# clapclap2313.net
KiCad netlist of a schematic drawn in EAGLE
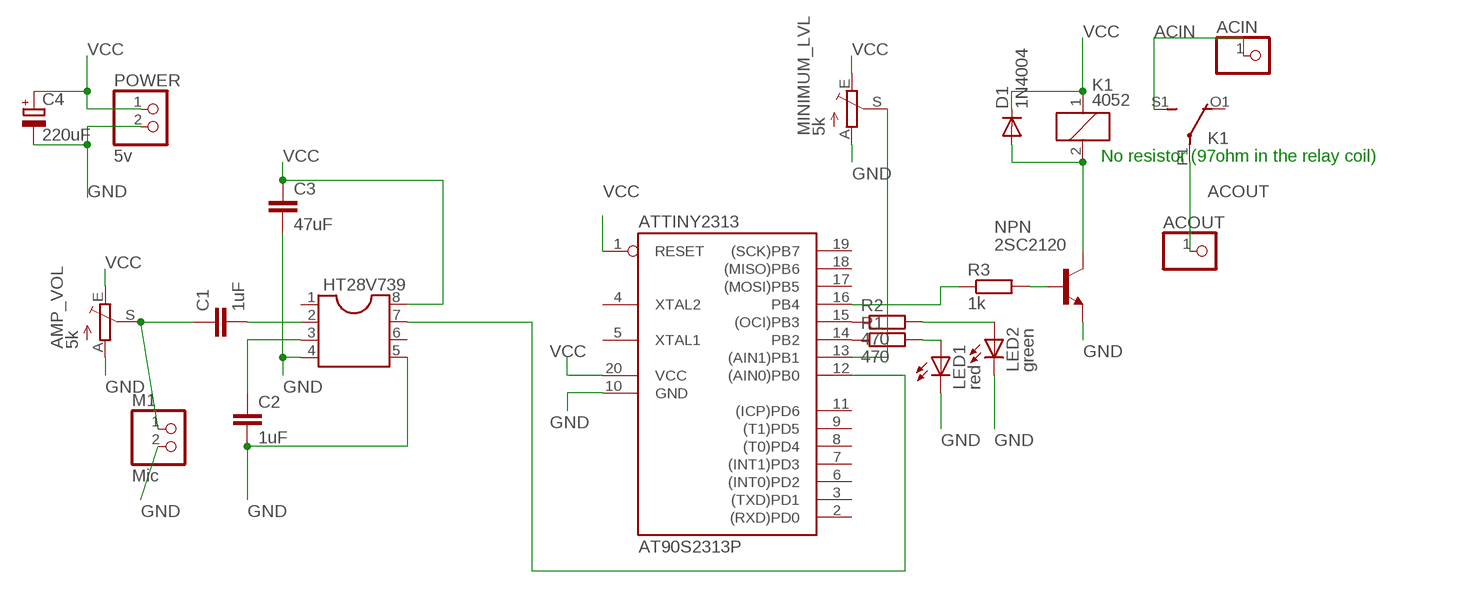
[diagram p0: schematic, sheet 1]

(export (version "E")
  (design (tool "Eeschema 10.0.6"))
  (components
    (comp (ref "ACIN")
      (value "PINHD-1X1")
      (footprint "eagle-import:1X01")
      (libsource (lib "eagle-import") (part "PINHD-1X1"))
    )
    (comp (ref "ACOUT")
      (value "PINHD-1X1")
      (footprint "eagle-import:1X01")
      (libsource (lib "eagle-import") (part "PINHD-1X1"))
    )
    (comp (ref "AMP_VOL")
      (value "5k")
      (footprint "eagle-import:CT6")
      (libsource (lib "eagle-import") (part "TRIM_EU-CT6"))
    )
    (comp (ref "ATTINY2313")
      (value "AT90S2313P")
      (footprint "eagle-import:DIL20")
      (libsource (lib "eagle-import") (part "AT90S2313P"))
    )
    (comp (ref "C1")
      (value "1uF")
      (footprint "eagle-import:C050-024X044")
      (libsource (lib "eagle-import") (part "C-EU050-024X044"))
    )
    (comp (ref "C2")
      (value "1uF")
      (footprint "eagle-import:C050-024X044")
      (libsource (lib "eagle-import") (part "C-EU050-024X044"))
    )
    (comp (ref "C3")
      (value "47uF")
      (footprint "eagle-import:C050-024X044")
      (libsource (lib "eagle-import") (part "C-EU050-024X044"))
    )
    (comp (ref "C4")
      (value "220uF")
      (footprint "eagle-import:E2,5-6E")
      (libsource (lib "eagle-import") (part "CPOL-EUE2,5-6E"))
    )
    (comp (ref "D1")
      (value "1N4004")
      (footprint "eagle-import:DO41-10")
      (libsource (lib "eagle-import") (part "1N4004"))
    )
    (comp (ref "HT28V739")
      (value "DIL8S")
      (footprint "eagle-import:SOCKET-08")
      (libsource (lib "eagle-import") (part "DIL8S"))
    )
    (comp (ref "K1")
      (value "4052")
      (footprint "eagle-import:F4052")
      (libsource (lib "eagle-import") (part "4052"))
    )
    (comp (ref "LED1")
      (value "red")
      (footprint "eagle-import:LED3MM")
      (libsource (lib "eagle-import") (part "LED3MM"))
    )
    (comp (ref "LED2")
      (value "green")
      (footprint "eagle-import:LED3MM")
      (libsource (lib "eagle-import") (part "LED3MM"))
    )
    (comp (ref "M1")
      (value "Mic")
      (footprint "eagle-import:1X02")
      (libsource (lib "eagle-import") (part "PINHD-1X2"))
    )
    (comp (ref "MINIMUM_LVL")
      (value "5k")
      (footprint "eagle-import:CT6")
      (libsource (lib "eagle-import") (part "TRIM_EU-CT6"))
    )
    (comp (ref "NPN")
      (value "2SC2120")
      (footprint "eagle-import:TO92-ECB")
      (libsource (lib "eagle-import") (part "-NPN-TO92-ECB"))
    )
    (comp (ref "POWER")
      (value "5v")
      (footprint "eagle-import:1X02")
      (libsource (lib "eagle-import") (part "PINHD-1X2"))
    )
    (comp (ref "R1")
      (value "470")
      (footprint "eagle-import:0204V")
      (libsource (lib "eagle-import") (part "R-EU_0204/2V"))
    )
    (comp (ref "R2")
      (value "470")
      (footprint "eagle-import:0204V")
      (libsource (lib "eagle-import") (part "R-EU_0204/2V"))
    )
    (comp (ref "R3")
      (value "1k")
      (footprint "eagle-import:0207_2V")
      (libsource (lib "eagle-import") (part "R-EU_0207/2V"))
    )
  )
  (nets
    (net (code "1") (name "/ACIN") (class "Default")
      (node (ref "ACIN") (pin "1") (pinfunction "1_1") (pintype "passive"))
      (node (ref "K1") (pin "S1") (pinfunction "S_S1") (pintype "passive"))
    )
    (net (code "2") (name "/ACOUT") (class "Default")
      (node (ref "ACOUT") (pin "1") (pinfunction "1_1") (pintype "passive"))
      (node (ref "K1") (pin "P1") (pinfunction "P_P1") (pintype "passive"))
    )
    (net (code "3") (name "/GND") (class "Default")
      (node (ref "AMP_VOL") (pin "A") (pinfunction "A_A") (pintype "passive"))
      (node (ref "ATTINY2313") (pin "10") (pinfunction "GND_10") (pintype "power_in"))
      (node (ref "C2") (pin "2") (pinfunction "2_2") (pintype "passive"))
      (node (ref "C3") (pin "2") (pinfunction "2_2") (pintype "passive"))
      (node (ref "C4") (pin "-") (pinfunction "-_-") (pintype "passive"))
      (node (ref "HT28V739") (pin "4") (pinfunction "4_4") (pintype "passive"))
      (node (ref "HT28V739") (pin "5") (pinfunction "5_5") (pintype "passive"))
      (node (ref "LED1") (pin "K") (pinfunction "C_K") (pintype "passive"))
      (node (ref "LED2") (pin "K") (pinfunction "C_K") (pintype "passive"))
      (node (ref "M1") (pin "2") (pinfunction "2_2") (pintype "passive"))
      (node (ref "MINIMUM_LVL") (pin "A") (pinfunction "A_A") (pintype "passive"))
      (node (ref "NPN") (pin "E") (pinfunction "E_E") (pintype "passive"))
      (node (ref "POWER") (pin "2") (pinfunction "2_2") (pintype "passive"))
    )
    (net (code "4") (name "/VCC") (class "Default")
      (node (ref "AMP_VOL") (pin "E") (pinfunction "E_E") (pintype "passive"))
      (node (ref "ATTINY2313") (pin "1") (pinfunction "RESET_1") (pintype "bidirectional"))
      (node (ref "ATTINY2313") (pin "20") (pinfunction "VCC_20") (pintype "power_in"))
      (node (ref "C3") (pin "1") (pinfunction "1_1") (pintype "passive"))
      (node (ref "C4") (pin "+") (pinfunction "+_+") (pintype "passive"))
      (node (ref "D1") (pin "C") (pinfunction "C_C") (pintype "passive"))
      (node (ref "HT28V739") (pin "8") (pinfunction "8_8") (pintype "passive"))
      (node (ref "K1") (pin "1") (pinfunction "1_1") (pintype "passive"))
      (node (ref "MINIMUM_LVL") (pin "E") (pinfunction "E_E") (pintype "passive"))
      (node (ref "POWER") (pin "1") (pinfunction "1_1") (pintype "passive"))
    )
    (net (code "5") (name "Net-(AMP_VOL-PadS)") (class "Default")
      (node (ref "AMP_VOL") (pin "S") (pinfunction "S_S") (pintype "passive"))
      (node (ref "C1") (pin "1") (pinfunction "1_1") (pintype "passive"))
      (node (ref "M1") (pin "1") (pinfunction "1_1") (pintype "passive"))
    )
    (net (code "6") (name "Net-(ATTINY2313-(AIN0)PB0)") (class "Default")
      (node (ref "ATTINY2313") (pin "12") (pinfunction "(AIN0)PB0_12") (pintype "bidirectional"))
      (node (ref "HT28V739") (pin "7") (pinfunction "7_7") (pintype "passive"))
    )
    (net (code "7") (name "Net-(ATTINY2313-(AIN1)PB1)") (class "Default")
      (node (ref "ATTINY2313") (pin "13") (pinfunction "(AIN1)PB1_13") (pintype "bidirectional"))
      (node (ref "MINIMUM_LVL") (pin "S") (pinfunction "S_S") (pintype "passive"))
    )
    (net (code "8") (name "Net-(ATTINY2313-(OCI)PB3)") (class "Default")
      (node (ref "ATTINY2313") (pin "15") (pinfunction "(OCI)PB3_15") (pintype "bidirectional"))
      (node (ref "R2") (pin "1") (pinfunction "1_1") (pintype "passive"))
    )
    (net (code "9") (name "Net-(ATTINY2313-PB2)") (class "Default")
      (node (ref "ATTINY2313") (pin "14") (pinfunction "PB2_14") (pintype "bidirectional"))
      (node (ref "R1") (pin "1") (pinfunction "1_1") (pintype "passive"))
    )
    (net (code "10") (name "Net-(ATTINY2313-PB4)") (class "Default")
      (node (ref "ATTINY2313") (pin "16") (pinfunction "PB4_16") (pintype "bidirectional"))
      (node (ref "R3") (pin "1") (pinfunction "1_1") (pintype "passive"))
    )
    (net (code "11") (name "Net-(C1-Pad2)") (class "Default")
      (node (ref "C1") (pin "2") (pinfunction "2_2") (pintype "passive"))
      (node (ref "HT28V739") (pin "2") (pinfunction "2_2") (pintype "passive"))
    )
    (net (code "12") (name "Net-(C2-Pad1)") (class "Default")
      (node (ref "C2") (pin "1") (pinfunction "1_1") (pintype "passive"))
      (node (ref "HT28V739") (pin "3") (pinfunction "3_3") (pintype "passive"))
    )
    (net (code "13") (name "Net-(D1-PadA)") (class "Default")
      (node (ref "D1") (pin "A") (pinfunction "A_A") (pintype "passive"))
      (node (ref "K1") (pin "2") (pinfunction "2_2") (pintype "passive"))
      (node (ref "NPN") (pin "C") (pinfunction "C_C") (pintype "passive"))
    )
    (net (code "14") (name "Net-(LED1-PadA)") (class "Default")
      (node (ref "LED1") (pin "A") (pinfunction "A_A") (pintype "passive"))
      (node (ref "R1") (pin "2") (pinfunction "2_2") (pintype "passive"))
    )
    (net (code "15") (name "Net-(LED2-PadA)") (class "Default")
      (node (ref "LED2") (pin "A") (pinfunction "A_A") (pintype "passive"))
      (node (ref "R2") (pin "2") (pinfunction "2_2") (pintype "passive"))
    )
    (net (code "16") (name "Net-(NPN-PadB)") (class "Default")
      (node (ref "NPN") (pin "B") (pinfunction "B_B") (pintype "passive"))
      (node (ref "R3") (pin "2") (pinfunction "2_2") (pintype "passive"))
    )
    (net (code "17") (name "unconnected-(ATTINY2313-(ICP)PD6-Pad11)") (class "Default")
      (node (ref "ATTINY2313") (pin "11") (pinfunction "(ICP)PD6_11") (pintype "bidirectional"))
    )
    (net (code "18") (name "unconnected-(ATTINY2313-(INT0)PD2-Pad6)") (class "Default")
      (node (ref "ATTINY2313") (pin "6") (pinfunction "(INT0)PD2_6") (pintype "bidirectional"))
    )
    (net (code "19") (name "unconnected-(ATTINY2313-(INT1)PD3-Pad7)") (class "Default")
      (node (ref "ATTINY2313") (pin "7") (pinfunction "(INT1)PD3_7") (pintype "bidirectional"))
    )
    (net (code "20") (name "unconnected-(ATTINY2313-(MISO)PB6-Pad18)") (class "Default")
      (node (ref "ATTINY2313") (pin "18") (pinfunction "(MISO)PB6_18") (pintype "bidirectional"))
    )
    (net (code "21") (name "unconnected-(ATTINY2313-(MOSI)PB5-Pad17)") (class "Default")
      (node (ref "ATTINY2313") (pin "17") (pinfunction "(MOSI)PB5_17") (pintype "bidirectional"))
    )
    (net (code "22") (name "unconnected-(ATTINY2313-(RXD)PD0-Pad2)") (class "Default")
      (node (ref "ATTINY2313") (pin "2") (pinfunction "(RXD)PD0_2") (pintype "bidirectional"))
    )
    (net (code "23") (name "unconnected-(ATTINY2313-(SCK)PB7-Pad19)") (class "Default")
      (node (ref "ATTINY2313") (pin "19") (pinfunction "(SCK)PB7_19") (pintype "bidirectional"))
    )
    (net (code "24") (name "unconnected-(ATTINY2313-(T0)PD4-Pad8)") (class "Default")
      (node (ref "ATTINY2313") (pin "8") (pinfunction "(T0)PD4_8") (pintype "bidirectional"))
    )
    (net (code "25") (name "unconnected-(ATTINY2313-(T1)PD5-Pad9)") (class "Default")
      (node (ref "ATTINY2313") (pin "9") (pinfunction "(T1)PD5_9") (pintype "bidirectional"))
    )
    (net (code "26") (name "unconnected-(ATTINY2313-(TXD)PD1-Pad3)") (class "Default")
      (node (ref "ATTINY2313") (pin "3") (pinfunction "(TXD)PD1_3") (pintype "bidirectional"))
    )
    (net (code "27") (name "unconnected-(ATTINY2313-XTAL1-Pad5)") (class "Default")
      (node (ref "ATTINY2313") (pin "5") (pinfunction "XTAL1_5") (pintype "bidirectional"))
    )
    (net (code "28") (name "unconnected-(ATTINY2313-XTAL2-Pad4)") (class "Default")
      (node (ref "ATTINY2313") (pin "4") (pinfunction "XTAL2_4") (pintype "bidirectional"))
    )
    (net (code "29") (name "unconnected-(HT28V739-Pad1)") (class "Default")
      (node (ref "HT28V739") (pin "1") (pinfunction "1_1") (pintype "passive"))
    )
    (net (code "30") (name "unconnected-(HT28V739-Pad6)") (class "Default")
      (node (ref "HT28V739") (pin "6") (pinfunction "6_6") (pintype "passive"))
    )
    (net (code "31") (name "unconnected-(K1B-O-PadO1)") (class "Default")
      (node (ref "K1") (pin "O1") (pinfunction "O_O1") (pintype "passive"))
    )
  )
)
